# Feather10DOF.net
KiCad netlist of a schematic drawn in EAGLE
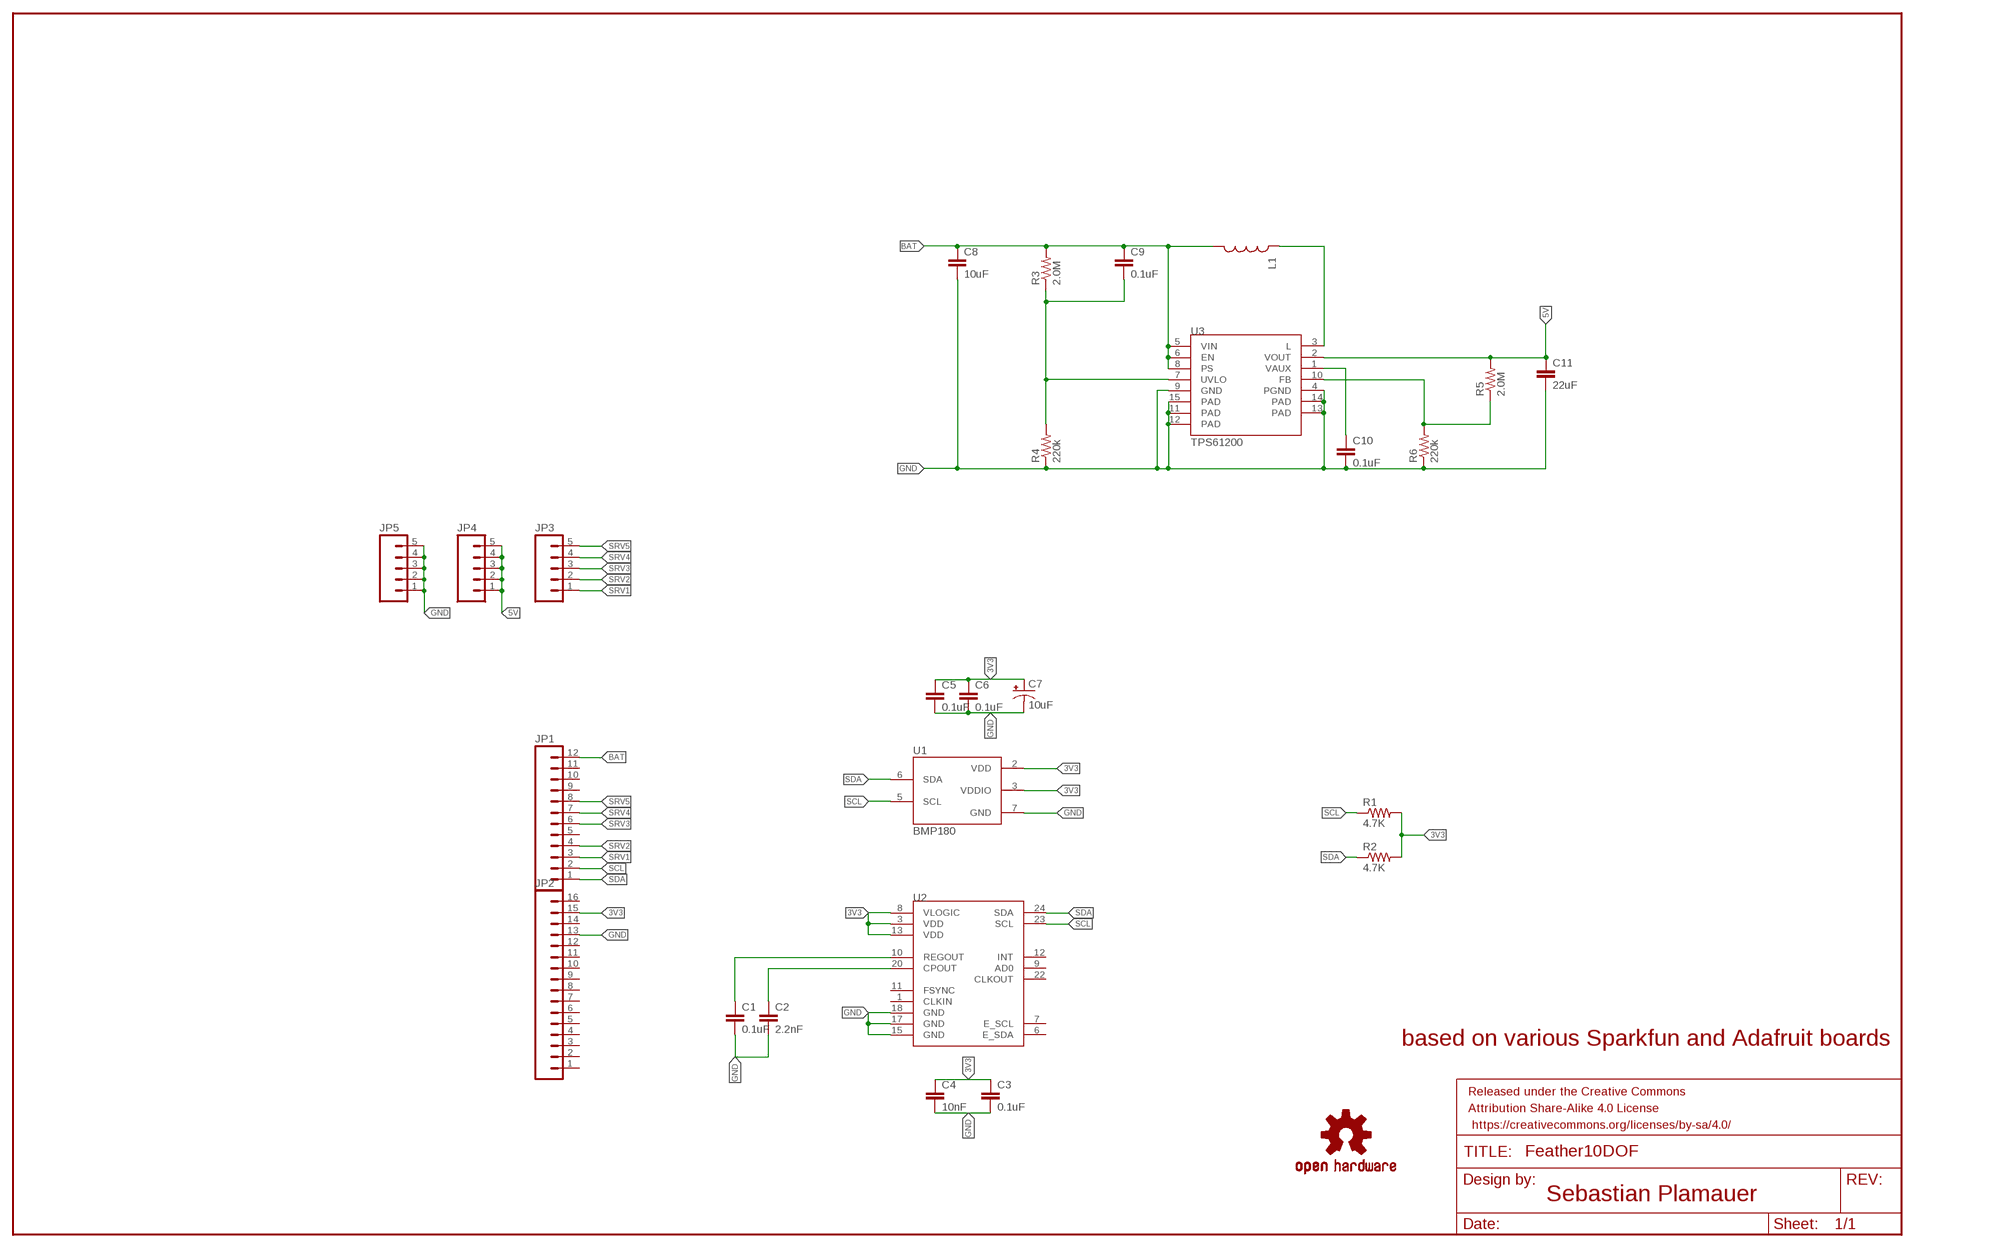
[diagram p0: schematic, sheet 1]

(export (version "E")
  (design (tool "Eeschema 10.0.6"))
  (components
    (comp (ref "C1")
      (value "0.1uF")
      (footprint "eagle-import:0603-CAP")
      (libsource (lib "eagle-import") (part "0.1UF-25V(+80/-20%)(0603)"))
    )
    (comp (ref "C2")
      (value "2.2nF")
      (footprint "eagle-import:0603-CAP")
      (libsource (lib "eagle-import") (part "2.2NF/2200PF-50V-10%(0603)"))
    )
    (comp (ref "C3")
      (value "0.1uF")
      (footprint "eagle-import:0603-CAP")
      (libsource (lib "eagle-import") (part "0.1UF-25V(+80/-20%)(0603)"))
    )
    (comp (ref "C4")
      (value "10nF")
      (footprint "eagle-import:0603-CAP")
      (libsource (lib "eagle-import") (part "10NF/10000PF-50V-10%(0603)"))
    )
    (comp (ref "C5")
      (value "0.1uF")
      (footprint "eagle-import:0603-CAP")
      (libsource (lib "eagle-import") (part "0.1UF-25V(+80/-20%)(0603)"))
    )
    (comp (ref "C6")
      (value "0.1uF")
      (footprint "eagle-import:0603-CAP")
      (libsource (lib "eagle-import") (part "0.1UF-25V(+80/-20%)(0603)"))
    )
    (comp (ref "C7")
      (value "10uF")
      (footprint "eagle-import:0603-POL")
      (libsource (lib "eagle-import") (part "10UF-6.3V-20%(0603)(TANT){dblquote}"))
    )
    (comp (ref "C8")
      (value "10uF")
      (footprint "eagle-import:0603-CAP")
      (libsource (lib "eagle-import") (part "10UF-6.3V-20%(0603)"))
    )
    (comp (ref "C9")
      (value "0.1uF")
      (footprint "eagle-import:0603-CAP")
      (libsource (lib "eagle-import") (part "0.1UF-25V(+80/-20%)(0603)"))
    )
    (comp (ref "C10")
      (value "0.1uF")
      (footprint "eagle-import:0603-CAP")
      (libsource (lib "eagle-import") (part "0.1UF-25V(+80/-20%)(0603)"))
    )
    (comp (ref "C11")
      (value "22uF")
      (footprint "eagle-import:0805")
      (libsource (lib "eagle-import") (part "22UF-6.3V-20%(0805)"))
    )
    (comp (ref "FRAME1")
      (value "FRAME-LEDGER")
      (footprint "eagle-import:CREATIVE_COMMONS")
      (libsource (lib "eagle-import") (part "FRAME-LEDGER"))
    )
    (comp (ref "JP1")
      (value "M12PTH")
      (footprint "eagle-import:1X12")
      (libsource (lib "eagle-import") (part "M12PTH"))
    )
    (comp (ref "JP2")
      (value "M16PTH")
      (footprint "eagle-import:1X16")
      (libsource (lib "eagle-import") (part "M16PTH"))
    )
    (comp (ref "JP3")
      (value "M05PTH")
      (footprint "eagle-import:1X05")
      (libsource (lib "eagle-import") (part "M05PTH"))
    )
    (comp (ref "JP4")
      (value "M05PTH")
      (footprint "eagle-import:1X05")
      (libsource (lib "eagle-import") (part "M05PTH"))
    )
    (comp (ref "JP5")
      (value "M05PTH")
      (footprint "eagle-import:1X05")
      (libsource (lib "eagle-import") (part "M05PTH"))
    )
    (comp (ref "L1")
      (value "INDUCTOR1007")
      (footprint "eagle-import:1007")
      (libsource (lib "eagle-import") (part "INDUCTOR1007"))
    )
    (comp (ref "LOGO1")
      (value "OSHW-LOGOL")
      (footprint "eagle-import:OSHW-LOGO-L")
      (libsource (lib "eagle-import") (part "OSHW-LOGOL"))
    )
    (comp (ref "R1")
      (value "4.7K")
      (footprint "eagle-import:0603-RES")
      (libsource (lib "eagle-import") (part "4.7KOHM-1/10W-1%(0603)"))
    )
    (comp (ref "R2")
      (value "4.7K")
      (footprint "eagle-import:0603-RES")
      (libsource (lib "eagle-import") (part "4.7KOHM-1/10W-1%(0603)"))
    )
    (comp (ref "R3")
      (value "2.0M")
      (footprint "eagle-import:0603-RES")
      (libsource (lib "eagle-import") (part "2MOHMS-1/10W-1%(0603)"))
    )
    (comp (ref "R4")
      (value "220k")
      (footprint "eagle-import:0603-RES")
      (libsource (lib "eagle-import") (part "220KOHM1/10W1%(0603)"))
    )
    (comp (ref "R5")
      (value "2.0M")
      (footprint "eagle-import:0603-RES")
      (libsource (lib "eagle-import") (part "2MOHMS-1/10W-1%(0603)"))
    )
    (comp (ref "R6")
      (value "220k")
      (footprint "eagle-import:0603-RES")
      (libsource (lib "eagle-import") (part "220KOHM1/10W1%(0603)"))
    )
    (comp (ref "U1")
      (value "BMP180")
      (footprint "eagle-import:BMP180")
      (libsource (lib "eagle-import") (part "BMP180"))
    )
    (comp (ref "U2")
      (value "MPU-9150QFN-24-NP")
      (footprint "eagle-import:QFN-24-NP")
      (libsource (lib "eagle-import") (part "MPU-9150QFN-24-NP"))
    )
    (comp (ref "U3")
      (value "TPS61200")
      (footprint "eagle-import:QFN-10_PAD")
      (libsource (lib "eagle-import") (part "TPS61200"))
    )
  )
  (nets
    (net (code "1") (name "3V3") (class "Default")
      (node (ref "C3") (pin "1") (pinfunction "1_1") (pintype "passive"))
      (node (ref "C4") (pin "1") (pinfunction "1_1") (pintype "passive"))
      (node (ref "C5") (pin "1") (pinfunction "1_1") (pintype "passive"))
      (node (ref "C6") (pin "1") (pinfunction "1_1") (pintype "passive"))
      (node (ref "C7") (pin "A") (pinfunction "+_A") (pintype "passive"))
      (node (ref "JP2") (pin "15") (pinfunction "15_15") (pintype "passive"))
      (node (ref "R1") (pin "2") (pinfunction "2_2") (pintype "passive"))
      (node (ref "R2") (pin "2") (pinfunction "2_2") (pintype "passive"))
      (node (ref "U1") (pin "2") (pinfunction "VDD_2") (pintype "power_in"))
      (node (ref "U1") (pin "3") (pinfunction "VDDIO_3") (pintype "power_in"))
      (node (ref "U2") (pin "13") (pinfunction "VDD_13") (pintype "bidirectional"))
      (node (ref "U2") (pin "3") (pinfunction "VDD_3") (pintype "bidirectional"))
      (node (ref "U2") (pin "8") (pinfunction "VLOGIC_8") (pintype "bidirectional"))
    )
    (net (code "2") (name "5V") (class "Default")
      (node (ref "C11") (pin "1") (pinfunction "1_1") (pintype "passive"))
      (node (ref "JP4") (pin "1") (pinfunction "1_1") (pintype "passive"))
      (node (ref "JP4") (pin "2") (pinfunction "2_2") (pintype "passive"))
      (node (ref "JP4") (pin "3") (pinfunction "3_3") (pintype "passive"))
      (node (ref "JP4") (pin "4") (pinfunction "4_4") (pintype "passive"))
      (node (ref "JP4") (pin "5") (pinfunction "5_5") (pintype "passive"))
      (node (ref "R5") (pin "2") (pinfunction "2_2") (pintype "passive"))
      (node (ref "U3") (pin "2") (pinfunction "VOUT_2") (pintype "passive"))
    )
    (net (code "3") (name "BAT") (class "Default")
      (node (ref "C8") (pin "1") (pinfunction "1_1") (pintype "passive"))
      (node (ref "C9") (pin "1") (pinfunction "1_1") (pintype "passive"))
      (node (ref "JP1") (pin "12") (pinfunction "12_12") (pintype "passive"))
      (node (ref "L1") (pin "2") (pinfunction "2_2") (pintype "passive"))
      (node (ref "R3") (pin "2") (pinfunction "2_2") (pintype "passive"))
      (node (ref "U3") (pin "5") (pinfunction "VIN_5") (pintype "power_in"))
      (node (ref "U3") (pin "6") (pinfunction "EN_6") (pintype "input"))
      (node (ref "U3") (pin "8") (pinfunction "PS_8") (pintype "input"))
    )
    (net (code "4") (name "GND") (class "Default")
      (node (ref "C1") (pin "2") (pinfunction "2_2") (pintype "passive"))
      (node (ref "C10") (pin "2") (pinfunction "2_2") (pintype "passive"))
      (node (ref "C11") (pin "2") (pinfunction "2_2") (pintype "passive"))
      (node (ref "C2") (pin "2") (pinfunction "2_2") (pintype "passive"))
      (node (ref "C3") (pin "2") (pinfunction "2_2") (pintype "passive"))
      (node (ref "C4") (pin "2") (pinfunction "2_2") (pintype "passive"))
      (node (ref "C5") (pin "2") (pinfunction "2_2") (pintype "passive"))
      (node (ref "C6") (pin "2") (pinfunction "2_2") (pintype "passive"))
      (node (ref "C7") (pin "K") (pinfunction "-_K") (pintype "passive"))
      (node (ref "C8") (pin "2") (pinfunction "2_2") (pintype "passive"))
      (node (ref "JP2") (pin "13") (pinfunction "13_13") (pintype "passive"))
      (node (ref "JP5") (pin "1") (pinfunction "1_1") (pintype "passive"))
      (node (ref "JP5") (pin "2") (pinfunction "2_2") (pintype "passive"))
      (node (ref "JP5") (pin "3") (pinfunction "3_3") (pintype "passive"))
      (node (ref "JP5") (pin "4") (pinfunction "4_4") (pintype "passive"))
      (node (ref "JP5") (pin "5") (pinfunction "5_5") (pintype "passive"))
      (node (ref "R4") (pin "1") (pinfunction "1_1") (pintype "passive"))
      (node (ref "R6") (pin "1") (pinfunction "1_1") (pintype "passive"))
      (node (ref "U1") (pin "7") (pinfunction "GND_7") (pintype "power_in"))
      (node (ref "U2") (pin "15") (pinfunction "GND_15") (pintype "bidirectional"))
      (node (ref "U2") (pin "17") (pinfunction "GND_17") (pintype "bidirectional"))
      (node (ref "U2") (pin "18") (pinfunction "GND_18") (pintype "bidirectional"))
      (node (ref "U3") (pin "11") (pinfunction "PAD_11") (pintype "power_in"))
      (node (ref "U3") (pin "12") (pinfunction "PAD_12") (pintype "power_in"))
      (node (ref "U3") (pin "13") (pinfunction "PAD_13") (pintype "power_in"))
      (node (ref "U3") (pin "14") (pinfunction "PAD_14") (pintype "power_in"))
      (node (ref "U3") (pin "15") (pinfunction "PAD_15") (pintype "power_in"))
      (node (ref "U3") (pin "4") (pinfunction "PGND_4") (pintype "power_in"))
      (node (ref "U3") (pin "9") (pinfunction "GND_9") (pintype "power_in"))
    )
    (net (code "5") (name "Net-(U2-CPOUT)") (class "Default")
      (node (ref "C2") (pin "1") (pinfunction "1_1") (pintype "passive"))
      (node (ref "U2") (pin "20") (pinfunction "CPOUT_20") (pintype "bidirectional"))
    )
    (net (code "6") (name "Net-(U2-REGOUT)") (class "Default")
      (node (ref "C1") (pin "1") (pinfunction "1_1") (pintype "passive"))
      (node (ref "U2") (pin "10") (pinfunction "REGOUT_10") (pintype "bidirectional"))
    )
    (net (code "7") (name "Net-(U3-FB)") (class "Default")
      (node (ref "R5") (pin "1") (pinfunction "1_1") (pintype "passive"))
      (node (ref "R6") (pin "2") (pinfunction "2_2") (pintype "passive"))
      (node (ref "U3") (pin "10") (pinfunction "FB_10") (pintype "passive"))
    )
    (net (code "8") (name "Net-(U3-L)") (class "Default")
      (node (ref "L1") (pin "1") (pinfunction "1_1") (pintype "passive"))
      (node (ref "U3") (pin "3") (pinfunction "L_3") (pintype "passive"))
    )
    (net (code "9") (name "Net-(U3-UVLO)") (class "Default")
      (node (ref "C9") (pin "2") (pinfunction "2_2") (pintype "passive"))
      (node (ref "R3") (pin "1") (pinfunction "1_1") (pintype "passive"))
      (node (ref "R4") (pin "2") (pinfunction "2_2") (pintype "passive"))
      (node (ref "U3") (pin "7") (pinfunction "UVLO_7") (pintype "passive"))
    )
    (net (code "10") (name "Net-(U3-VAUX)") (class "Default")
      (node (ref "C10") (pin "1") (pinfunction "1_1") (pintype "passive"))
      (node (ref "U3") (pin "1") (pinfunction "VAUX_1") (pintype "passive"))
    )
    (net (code "11") (name "SCL") (class "Default")
      (node (ref "JP1") (pin "2") (pinfunction "2_2") (pintype "passive"))
      (node (ref "R1") (pin "1") (pinfunction "1_1") (pintype "passive"))
      (node (ref "U1") (pin "5") (pinfunction "SCL_5") (pintype "input"))
      (node (ref "U2") (pin "23") (pinfunction "SCL_23") (pintype "bidirectional"))
    )
    (net (code "12") (name "SDA") (class "Default")
      (node (ref "JP1") (pin "1") (pinfunction "1_1") (pintype "passive"))
      (node (ref "R2") (pin "1") (pinfunction "1_1") (pintype "passive"))
      (node (ref "U1") (pin "6") (pinfunction "SDA_6") (pintype "bidirectional"))
      (node (ref "U2") (pin "24") (pinfunction "SDA_24") (pintype "bidirectional"))
    )
    (net (code "13") (name "SRV1") (class "Default")
      (node (ref "JP1") (pin "3") (pinfunction "3_3") (pintype "passive"))
      (node (ref "JP3") (pin "1") (pinfunction "1_1") (pintype "passive"))
    )
    (net (code "14") (name "SRV2") (class "Default")
      (node (ref "JP1") (pin "4") (pinfunction "4_4") (pintype "passive"))
      (node (ref "JP3") (pin "2") (pinfunction "2_2") (pintype "passive"))
    )
    (net (code "15") (name "SRV3") (class "Default")
      (node (ref "JP1") (pin "6") (pinfunction "6_6") (pintype "passive"))
      (node (ref "JP3") (pin "3") (pinfunction "3_3") (pintype "passive"))
    )
    (net (code "16") (name "SRV4") (class "Default")
      (node (ref "JP1") (pin "7") (pinfunction "7_7") (pintype "passive"))
      (node (ref "JP3") (pin "4") (pinfunction "4_4") (pintype "passive"))
    )
    (net (code "17") (name "SRV5") (class "Default")
      (node (ref "JP1") (pin "8") (pinfunction "8_8") (pintype "passive"))
      (node (ref "JP3") (pin "5") (pinfunction "5_5") (pintype "passive"))
    )
    (net (code "18") (name "unconnected-(JP1-Pad5)") (class "Default")
      (node (ref "JP1") (pin "5") (pinfunction "5_5") (pintype "passive"))
    )
    (net (code "19") (name "unconnected-(JP1-Pad9)") (class "Default")
      (node (ref "JP1") (pin "9") (pinfunction "9_9") (pintype "passive"))
    )
    (net (code "20") (name "unconnected-(JP1-Pad10)") (class "Default")
      (node (ref "JP1") (pin "10") (pinfunction "10_10") (pintype "passive"))
    )
    (net (code "21") (name "unconnected-(JP1-Pad11)") (class "Default")
      (node (ref "JP1") (pin "11") (pinfunction "11_11") (pintype "passive"))
    )
    (net (code "22") (name "unconnected-(JP2-Pad1)") (class "Default")
      (node (ref "JP2") (pin "1") (pinfunction "1_1") (pintype "passive"))
    )
    (net (code "23") (name "unconnected-(JP2-Pad2)") (class "Default")
      (node (ref "JP2") (pin "2") (pinfunction "2_2") (pintype "passive"))
    )
    (net (code "24") (name "unconnected-(JP2-Pad3)") (class "Default")
      (node (ref "JP2") (pin "3") (pinfunction "3_3") (pintype "passive"))
    )
    (net (code "25") (name "unconnected-(JP2-Pad4)") (class "Default")
      (node (ref "JP2") (pin "4") (pinfunction "4_4") (pintype "passive"))
    )
    (net (code "26") (name "unconnected-(JP2-Pad5)") (class "Default")
      (node (ref "JP2") (pin "5") (pinfunction "5_5") (pintype "passive"))
    )
    (net (code "27") (name "unconnected-(JP2-Pad6)") (class "Default")
      (node (ref "JP2") (pin "6") (pinfunction "6_6") (pintype "passive"))
    )
    (net (code "28") (name "unconnected-(JP2-Pad7)") (class "Default")
      (node (ref "JP2") (pin "7") (pinfunction "7_7") (pintype "passive"))
    )
    (net (code "29") (name "unconnected-(JP2-Pad8)") (class "Default")
      (node (ref "JP2") (pin "8") (pinfunction "8_8") (pintype "passive"))
    )
    (net (code "30") (name "unconnected-(JP2-Pad9)") (class "Default")
      (node (ref "JP2") (pin "9") (pinfunction "9_9") (pintype "passive"))
    )
    (net (code "31") (name "unconnected-(JP2-Pad10)") (class "Default")
      (node (ref "JP2") (pin "10") (pinfunction "10_10") (pintype "passive"))
    )
    (net (code "32") (name "unconnected-(JP2-Pad11)") (class "Default")
      (node (ref "JP2") (pin "11") (pinfunction "11_11") (pintype "passive"))
    )
    (net (code "33") (name "unconnected-(JP2-Pad12)") (class "Default")
      (node (ref "JP2") (pin "12") (pinfunction "12_12") (pintype "passive"))
    )
    (net (code "34") (name "unconnected-(JP2-Pad14)") (class "Default")
      (node (ref "JP2") (pin "14") (pinfunction "14_14") (pintype "passive"))
    )
    (net (code "35") (name "unconnected-(JP2-Pad16)") (class "Default")
      (node (ref "JP2") (pin "16") (pinfunction "16_16") (pintype "passive"))
    )
    (net (code "36") (name "unconnected-(U2-AD0-Pad9)") (class "Default")
      (node (ref "U2") (pin "9") (pinfunction "AD0_9") (pintype "bidirectional"))
    )
    (net (code "37") (name "unconnected-(U2-CLKIN-Pad1)") (class "Default")
      (node (ref "U2") (pin "1") (pinfunction "CLKIN_1") (pintype "bidirectional"))
    )
    (net (code "38") (name "unconnected-(U2-CLKOUT-Pad22)") (class "Default")
      (node (ref "U2") (pin "22") (pinfunction "CLKOUT_22") (pintype "bidirectional"))
    )
    (net (code "39") (name "unconnected-(U2-E_SCL-Pad7)") (class "Default")
      (node (ref "U2") (pin "7") (pinfunction "E_SCL_7") (pintype "bidirectional"))
    )
    (net (code "40") (name "unconnected-(U2-E_SDA-Pad6)") (class "Default")
      (node (ref "U2") (pin "6") (pinfunction "E_SDA_6") (pintype "bidirectional"))
    )
    (net (code "41") (name "unconnected-(U2-FSYNC-Pad11)") (class "Default")
      (node (ref "U2") (pin "11") (pinfunction "FSYNC_11") (pintype "bidirectional"))
    )
    (net (code "42") (name "unconnected-(U2-INT-Pad12)") (class "Default")
      (node (ref "U2") (pin "12") (pinfunction "INT_12") (pintype "bidirectional"))
    )
  )
)
